# LESR.net
KiCad netlist of a schematic drawn in EAGLE
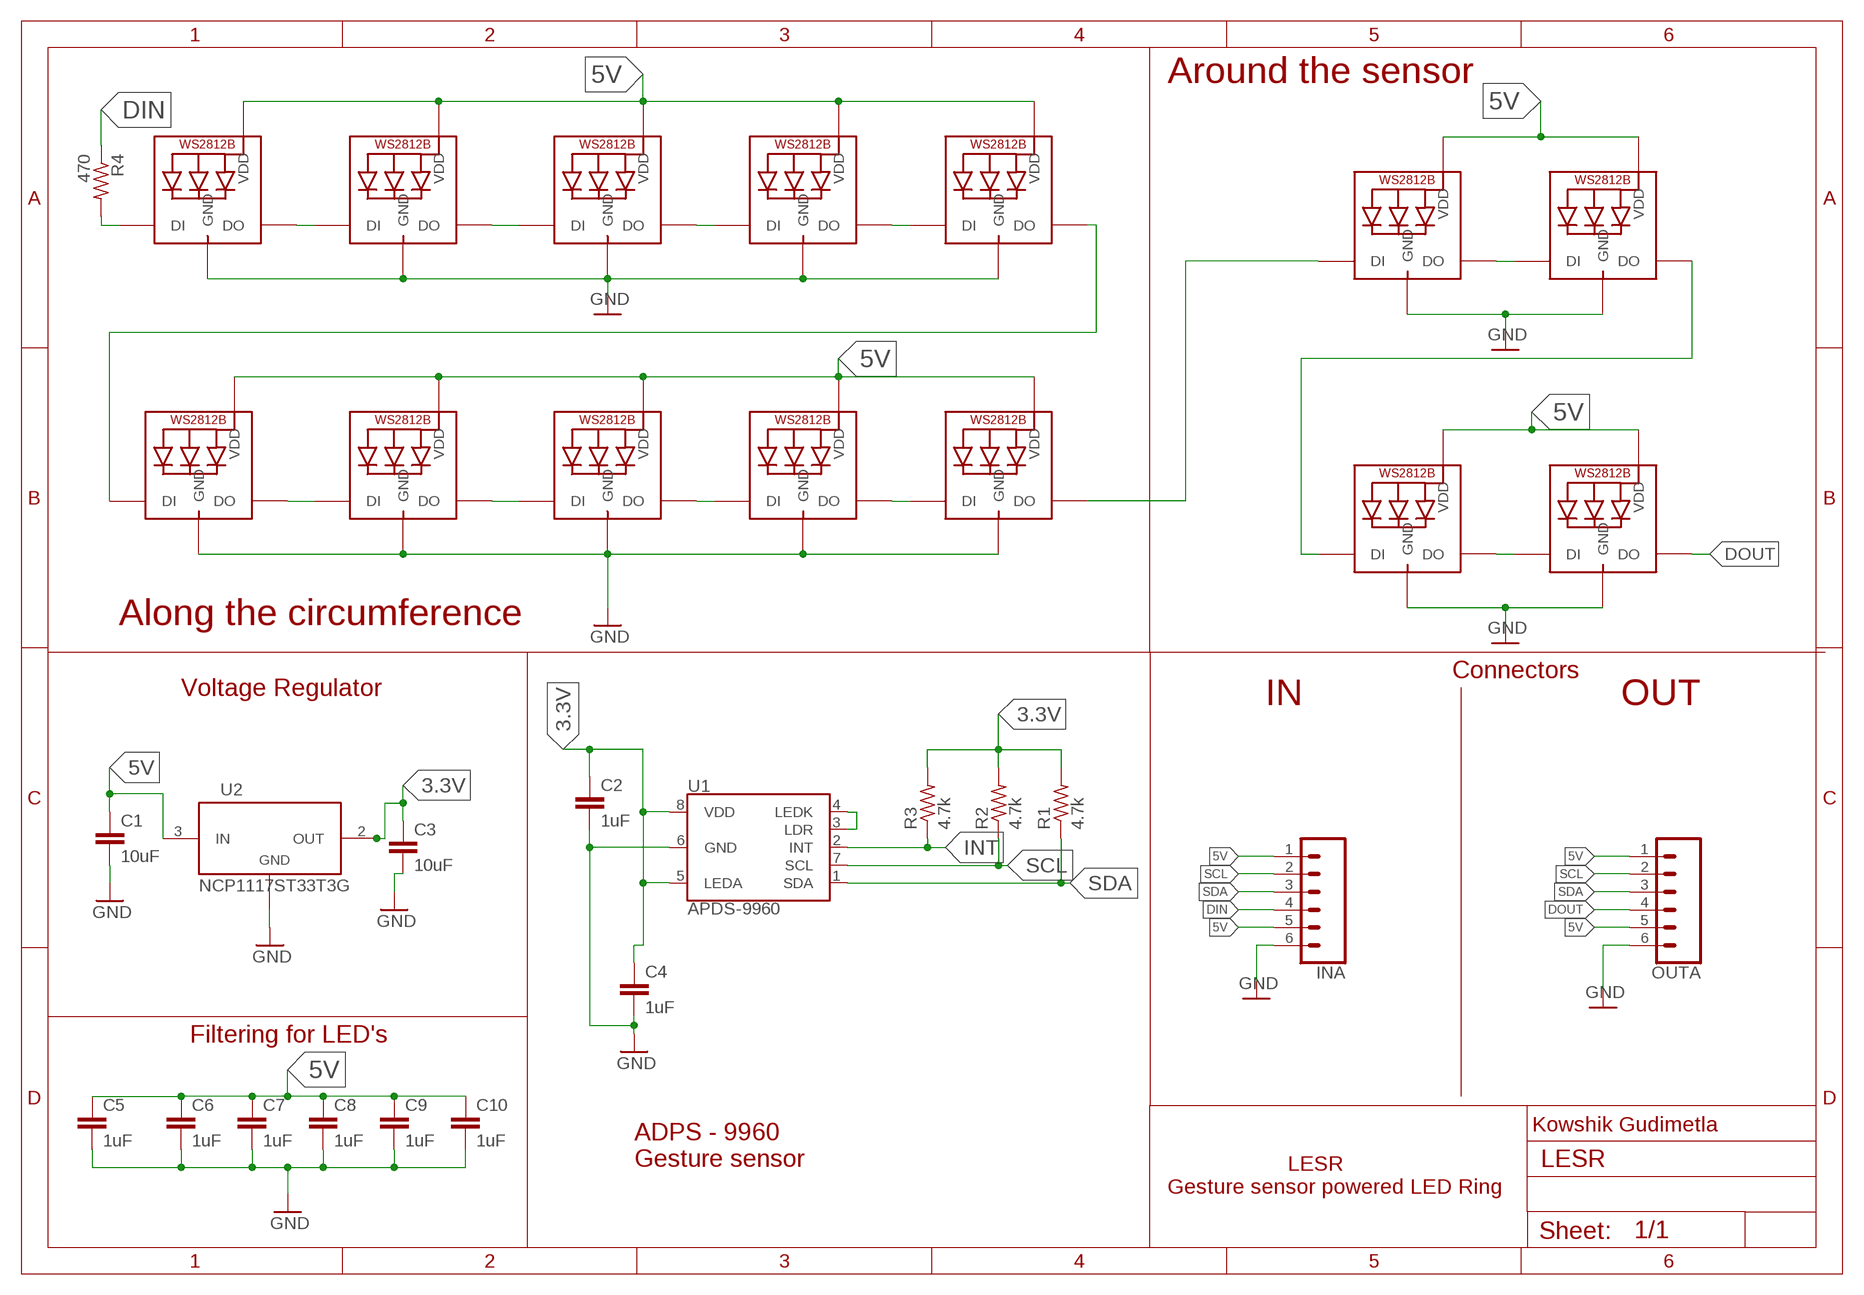
[diagram p0: schematic, sheet 1]

(export (version "E")
  (design (tool "Eeschema 10.0.6"))
  (components
    (comp (ref "C1")
      (value "10uF")
      (footprint "eagle-import:C0603")
      (libsource (lib "eagle-import") (part "C-EUC0603"))
    )
    (comp (ref "C2")
      (value "1uF")
      (footprint "eagle-import:C0603")
      (libsource (lib "eagle-import") (part "C-EUC0603"))
    )
    (comp (ref "C3")
      (value "10uF")
      (footprint "eagle-import:C0603")
      (libsource (lib "eagle-import") (part "C-EUC0603"))
    )
    (comp (ref "C4")
      (value "1uF")
      (footprint "eagle-import:C0603")
      (libsource (lib "eagle-import") (part "C-EUC0603"))
    )
    (comp (ref "C5")
      (value "1uF")
      (footprint "eagle-import:C0603")
      (libsource (lib "eagle-import") (part "C-EUC0603"))
    )
    (comp (ref "C6")
      (value "1uF")
      (footprint "eagle-import:C0603")
      (libsource (lib "eagle-import") (part "C-EUC0603"))
    )
    (comp (ref "C7")
      (value "1uF")
      (footprint "eagle-import:C0603")
      (libsource (lib "eagle-import") (part "C-EUC0603"))
    )
    (comp (ref "C8")
      (value "1uF")
      (footprint "eagle-import:C0603")
      (libsource (lib "eagle-import") (part "C-EUC0603"))
    )
    (comp (ref "C9")
      (value "1uF")
      (footprint "eagle-import:C0603")
      (libsource (lib "eagle-import") (part "C-EUC0603"))
    )
    (comp (ref "C10")
      (value "1uF")
      (footprint "eagle-import:C0603")
      (libsource (lib "eagle-import") (part "C-EUC0603"))
    )
    (comp (ref "IN")
      (value "BM06B-SRSS-TB")
      (footprint "eagle-import:JST-6-SMD-HORI-1.0MM")
      (libsource (lib "eagle-import") (part "JST_6_PIN_HORIZONTAL"))
    )
    (comp (ref "LED1")
      (value "WS2812B5050")
      (footprint "eagle-import:WS2812B")
      (fields (field (name "MF") "SparkFun Electronics") (field (name "MP") "WS2812B"))
      (libsource (lib "eagle-import") (part "WS2812B5050"))
    )
    (comp (ref "LED2")
      (value "WS2812B5050")
      (footprint "eagle-import:WS2812B")
      (fields (field (name "MF") "SparkFun Electronics") (field (name "MP") "WS2812B"))
      (libsource (lib "eagle-import") (part "WS2812B5050"))
    )
    (comp (ref "LED3")
      (value "WS2812B5050")
      (footprint "eagle-import:WS2812B")
      (fields (field (name "MF") "SparkFun Electronics") (field (name "MP") "WS2812B"))
      (libsource (lib "eagle-import") (part "WS2812B5050"))
    )
    (comp (ref "LED4")
      (value "WS2812B5050")
      (footprint "eagle-import:WS2812B")
      (fields (field (name "MF") "SparkFun Electronics") (field (name "MP") "WS2812B"))
      (libsource (lib "eagle-import") (part "WS2812B5050"))
    )
    (comp (ref "LED5")
      (value "WS2812B5050")
      (footprint "eagle-import:WS2812B")
      (fields (field (name "MF") "SparkFun Electronics") (field (name "MP") "WS2812B"))
      (libsource (lib "eagle-import") (part "WS2812B5050"))
    )
    (comp (ref "LED6")
      (value "WS2812B5050")
      (footprint "eagle-import:WS2812B")
      (fields (field (name "MF") "SparkFun Electronics") (field (name "MP") "WS2812B"))
      (libsource (lib "eagle-import") (part "WS2812B5050"))
    )
    (comp (ref "LED7")
      (value "WS2812B5050")
      (footprint "eagle-import:WS2812B")
      (fields (field (name "MF") "SparkFun Electronics") (field (name "MP") "WS2812B"))
      (libsource (lib "eagle-import") (part "WS2812B5050"))
    )
    (comp (ref "LED8")
      (value "WS2812B5050")
      (footprint "eagle-import:WS2812B")
      (fields (field (name "MF") "SparkFun Electronics") (field (name "MP") "WS2812B"))
      (libsource (lib "eagle-import") (part "WS2812B5050"))
    )
    (comp (ref "LED9")
      (value "WS2812B5050")
      (footprint "eagle-import:WS2812B")
      (fields (field (name "MF") "SparkFun Electronics") (field (name "MP") "WS2812B"))
      (libsource (lib "eagle-import") (part "WS2812B5050"))
    )
    (comp (ref "LED10")
      (value "WS2812B5050")
      (footprint "eagle-import:WS2812B")
      (fields (field (name "MF") "SparkFun Electronics") (field (name "MP") "WS2812B"))
      (libsource (lib "eagle-import") (part "WS2812B5050"))
    )
    (comp (ref "LED11")
      (value "WS2812B5050")
      (footprint "eagle-import:WS2812B")
      (fields (field (name "MF") "SparkFun Electronics") (field (name "MP") "WS2812B"))
      (libsource (lib "eagle-import") (part "WS2812B5050"))
    )
    (comp (ref "LED12")
      (value "WS2812B5050")
      (footprint "eagle-import:WS2812B")
      (fields (field (name "MF") "SparkFun Electronics") (field (name "MP") "WS2812B"))
      (libsource (lib "eagle-import") (part "WS2812B5050"))
    )
    (comp (ref "LED13")
      (value "WS2812B5050")
      (footprint "eagle-import:WS2812B")
      (fields (field (name "MF") "SparkFun Electronics") (field (name "MP") "WS2812B"))
      (libsource (lib "eagle-import") (part "WS2812B5050"))
    )
    (comp (ref "LED14")
      (value "WS2812B5050")
      (footprint "eagle-import:WS2812B")
      (fields (field (name "MF") "SparkFun Electronics") (field (name "MP") "WS2812B"))
      (libsource (lib "eagle-import") (part "WS2812B5050"))
    )
    (comp (ref "OUT")
      (value "BM06B-SRSS-TB")
      (footprint "eagle-import:JST-6-SMD-HORI-1.0MM")
      (libsource (lib "eagle-import") (part "JST_6_PIN_HORIZONTAL"))
    )
    (comp (ref "R1")
      (value "4.7k")
      (footprint "eagle-import:R0603")
      (libsource (lib "eagle-import") (part "R-US_R0603"))
    )
    (comp (ref "R2")
      (value "4.7k")
      (footprint "eagle-import:R0603")
      (libsource (lib "eagle-import") (part "R-US_R0603"))
    )
    (comp (ref "R3")
      (value "4.7k")
      (footprint "eagle-import:R0603")
      (libsource (lib "eagle-import") (part "R-US_R0603"))
    )
    (comp (ref "R4")
      (value "470")
      (footprint "eagle-import:R0603")
      (libsource (lib "eagle-import") (part "R-US_R0603"))
    )
    (comp (ref "U1")
      (value "APDS-9960")
      (footprint "eagle-import:APDS-9960")
      (fields (field (name "MF") "Broadcom Limited"))
      (libsource (lib "eagle-import") (part "APDS-9960"))
    )
    (comp (ref "U2")
      (value "NCP1117ST33T3G")
      (footprint "eagle-import:SOT-223")
      (fields
        (field (name "DIGIKEY_PART_NUMBER") "NCP1117ST33T3GOSTR-ND")
        (field (name "MANUFACTURER") "ON Semiconductor")
        (field (name "CREATED_BY") "PCBLayout.com")
      )
      (libsource (lib "eagle-import") (part "NCP1117ST33T3G"))
    )
  )
  (nets
    (net (code "1") (name "3.3V") (class "Default")
      (node (ref "C2") (pin "1") (pinfunction "1_1") (pintype "passive"))
      (node (ref "C3") (pin "1") (pinfunction "1_1") (pintype "passive"))
      (node (ref "C4") (pin "1") (pinfunction "1_1") (pintype "passive"))
      (node (ref "R1") (pin "2") (pinfunction "2_2") (pintype "passive"))
      (node (ref "R2") (pin "2") (pinfunction "2_2") (pintype "passive"))
      (node (ref "R3") (pin "2") (pinfunction "2_2") (pintype "passive"))
      (node (ref "U1") (pin "5") (pinfunction "LEDA_5") (pintype "bidirectional"))
      (node (ref "U1") (pin "8") (pinfunction "VDD_8") (pintype "bidirectional"))
      (node (ref "U2") (pin "2") (pinfunction "OUT_2") (pintype "output"))
      (node (ref "U2") (pin "4") (pinfunction "4_4") (pintype "passive"))
    )
    (net (code "2") (name "5V") (class "Default")
      (node (ref "C1") (pin "1") (pinfunction "1_1") (pintype "passive"))
      (node (ref "C10") (pin "1") (pinfunction "1_1") (pintype "passive"))
      (node (ref "C5") (pin "1") (pinfunction "1_1") (pintype "passive"))
      (node (ref "C6") (pin "1") (pinfunction "1_1") (pintype "passive"))
      (node (ref "C7") (pin "1") (pinfunction "1_1") (pintype "passive"))
      (node (ref "C8") (pin "1") (pinfunction "1_1") (pintype "passive"))
      (node (ref "C9") (pin "1") (pinfunction "1_1") (pintype "passive"))
      (node (ref "IN") (pin "1") (pinfunction "1_1") (pintype "passive"))
      (node (ref "IN") (pin "5") (pinfunction "5_5") (pintype "passive"))
      (node (ref "LED1") (pin "1-VDD") (pinfunction "VDD_1-VDD") (pintype "power_in"))
      (node (ref "LED10") (pin "1-VDD") (pinfunction "VDD_1-VDD") (pintype "power_in"))
      (node (ref "LED11") (pin "1-VDD") (pinfunction "VDD_1-VDD") (pintype "power_in"))
      (node (ref "LED12") (pin "1-VDD") (pinfunction "VDD_1-VDD") (pintype "power_in"))
      (node (ref "LED13") (pin "1-VDD") (pinfunction "VDD_1-VDD") (pintype "power_in"))
      (node (ref "LED14") (pin "1-VDD") (pinfunction "VDD_1-VDD") (pintype "power_in"))
      (node (ref "LED2") (pin "1-VDD") (pinfunction "VDD_1-VDD") (pintype "power_in"))
      (node (ref "LED3") (pin "1-VDD") (pinfunction "VDD_1-VDD") (pintype "power_in"))
      (node (ref "LED4") (pin "1-VDD") (pinfunction "VDD_1-VDD") (pintype "power_in"))
      (node (ref "LED5") (pin "1-VDD") (pinfunction "VDD_1-VDD") (pintype "power_in"))
      (node (ref "LED6") (pin "1-VDD") (pinfunction "VDD_1-VDD") (pintype "power_in"))
      (node (ref "LED7") (pin "1-VDD") (pinfunction "VDD_1-VDD") (pintype "power_in"))
      (node (ref "LED8") (pin "1-VDD") (pinfunction "VDD_1-VDD") (pintype "power_in"))
      (node (ref "LED9") (pin "1-VDD") (pinfunction "VDD_1-VDD") (pintype "power_in"))
      (node (ref "OUT") (pin "1") (pinfunction "1_1") (pintype "passive"))
      (node (ref "OUT") (pin "5") (pinfunction "5_5") (pintype "passive"))
      (node (ref "U2") (pin "3") (pinfunction "IN_3") (pintype "input"))
    )
    (net (code "3") (name "DIN") (class "Default")
      (node (ref "IN") (pin "4") (pinfunction "4_4") (pintype "passive"))
      (node (ref "R4") (pin "1") (pinfunction "1_1") (pintype "passive"))
    )
    (net (code "4") (name "DOUT") (class "Default")
      (node (ref "LED14") (pin "2-DOUT") (pinfunction "DO_2-DOUT") (pintype "output"))
      (node (ref "OUT") (pin "4") (pinfunction "4_4") (pintype "passive"))
    )
    (net (code "5") (name "GND") (class "Default")
      (node (ref "C1") (pin "2") (pinfunction "2_2") (pintype "passive"))
      (node (ref "C10") (pin "2") (pinfunction "2_2") (pintype "passive"))
      (node (ref "C2") (pin "2") (pinfunction "2_2") (pintype "passive"))
      (node (ref "C3") (pin "2") (pinfunction "2_2") (pintype "passive"))
      (node (ref "C4") (pin "2") (pinfunction "2_2") (pintype "passive"))
      (node (ref "C5") (pin "2") (pinfunction "2_2") (pintype "passive"))
      (node (ref "C6") (pin "2") (pinfunction "2_2") (pintype "passive"))
      (node (ref "C7") (pin "2") (pinfunction "2_2") (pintype "passive"))
      (node (ref "C8") (pin "2") (pinfunction "2_2") (pintype "passive"))
      (node (ref "C9") (pin "2") (pinfunction "2_2") (pintype "passive"))
      (node (ref "IN") (pin "6") (pinfunction "6_6") (pintype "passive"))
      (node (ref "LED1") (pin "3-GND") (pinfunction "GND_3-GND") (pintype "power_in"))
      (node (ref "LED10") (pin "3-GND") (pinfunction "GND_3-GND") (pintype "power_in"))
      (node (ref "LED11") (pin "3-GND") (pinfunction "GND_3-GND") (pintype "power_in"))
      (node (ref "LED12") (pin "3-GND") (pinfunction "GND_3-GND") (pintype "power_in"))
      (node (ref "LED13") (pin "3-GND") (pinfunction "GND_3-GND") (pintype "power_in"))
      (node (ref "LED14") (pin "3-GND") (pinfunction "GND_3-GND") (pintype "power_in"))
      (node (ref "LED2") (pin "3-GND") (pinfunction "GND_3-GND") (pintype "power_in"))
      (node (ref "LED3") (pin "3-GND") (pinfunction "GND_3-GND") (pintype "power_in"))
      (node (ref "LED4") (pin "3-GND") (pinfunction "GND_3-GND") (pintype "power_in"))
      (node (ref "LED5") (pin "3-GND") (pinfunction "GND_3-GND") (pintype "power_in"))
      (node (ref "LED6") (pin "3-GND") (pinfunction "GND_3-GND") (pintype "power_in"))
      (node (ref "LED7") (pin "3-GND") (pinfunction "GND_3-GND") (pintype "power_in"))
      (node (ref "LED8") (pin "3-GND") (pinfunction "GND_3-GND") (pintype "power_in"))
      (node (ref "LED9") (pin "3-GND") (pinfunction "GND_3-GND") (pintype "power_in"))
      (node (ref "OUT") (pin "6") (pinfunction "6_6") (pintype "passive"))
      (node (ref "U1") (pin "6") (pinfunction "GND_6") (pintype "bidirectional"))
      (node (ref "U2") (pin "1") (pinfunction "ADJ/GND_1") (pintype "power_in"))
    )
    (net (code "6") (name "INT") (class "Default")
      (node (ref "R3") (pin "1") (pinfunction "1_1") (pintype "passive"))
      (node (ref "U1") (pin "2") (pinfunction "INT_2") (pintype "bidirectional"))
    )
    (net (code "7") (name "Net-(LED1-DI)") (class "Default")
      (node (ref "LED1") (pin "4-DIN") (pinfunction "DI_4-DIN") (pintype "input"))
      (node (ref "R4") (pin "2") (pinfunction "2_2") (pintype "passive"))
    )
    (net (code "8") (name "Net-(LED1-DO)") (class "Default")
      (node (ref "LED1") (pin "2-DOUT") (pinfunction "DO_2-DOUT") (pintype "output"))
      (node (ref "LED2") (pin "4-DIN") (pinfunction "DI_4-DIN") (pintype "input"))
    )
    (net (code "9") (name "Net-(LED2-DO)") (class "Default")
      (node (ref "LED2") (pin "2-DOUT") (pinfunction "DO_2-DOUT") (pintype "output"))
      (node (ref "LED3") (pin "4-DIN") (pinfunction "DI_4-DIN") (pintype "input"))
    )
    (net (code "10") (name "Net-(LED3-DO)") (class "Default")
      (node (ref "LED3") (pin "2-DOUT") (pinfunction "DO_2-DOUT") (pintype "output"))
      (node (ref "LED4") (pin "4-DIN") (pinfunction "DI_4-DIN") (pintype "input"))
    )
    (net (code "11") (name "Net-(LED4-DO)") (class "Default")
      (node (ref "LED4") (pin "2-DOUT") (pinfunction "DO_2-DOUT") (pintype "output"))
      (node (ref "LED5") (pin "4-DIN") (pinfunction "DI_4-DIN") (pintype "input"))
    )
    (net (code "12") (name "Net-(LED5-DO)") (class "Default")
      (node (ref "LED5") (pin "2-DOUT") (pinfunction "DO_2-DOUT") (pintype "output"))
      (node (ref "LED6") (pin "4-DIN") (pinfunction "DI_4-DIN") (pintype "input"))
    )
    (net (code "13") (name "Net-(LED6-DO)") (class "Default")
      (node (ref "LED6") (pin "2-DOUT") (pinfunction "DO_2-DOUT") (pintype "output"))
      (node (ref "LED7") (pin "4-DIN") (pinfunction "DI_4-DIN") (pintype "input"))
    )
    (net (code "14") (name "Net-(LED7-DO)") (class "Default")
      (node (ref "LED7") (pin "2-DOUT") (pinfunction "DO_2-DOUT") (pintype "output"))
      (node (ref "LED8") (pin "4-DIN") (pinfunction "DI_4-DIN") (pintype "input"))
    )
    (net (code "15") (name "Net-(LED8-DO)") (class "Default")
      (node (ref "LED8") (pin "2-DOUT") (pinfunction "DO_2-DOUT") (pintype "output"))
      (node (ref "LED9") (pin "4-DIN") (pinfunction "DI_4-DIN") (pintype "input"))
    )
    (net (code "16") (name "Net-(LED10-DI)") (class "Default")
      (node (ref "LED10") (pin "4-DIN") (pinfunction "DI_4-DIN") (pintype "input"))
      (node (ref "LED9") (pin "2-DOUT") (pinfunction "DO_2-DOUT") (pintype "output"))
    )
    (net (code "17") (name "Net-(LED10-DO)") (class "Default")
      (node (ref "LED10") (pin "2-DOUT") (pinfunction "DO_2-DOUT") (pintype "output"))
      (node (ref "LED11") (pin "4-DIN") (pinfunction "DI_4-DIN") (pintype "input"))
    )
    (net (code "18") (name "Net-(LED11-DO)") (class "Default")
      (node (ref "LED11") (pin "2-DOUT") (pinfunction "DO_2-DOUT") (pintype "output"))
      (node (ref "LED12") (pin "4-DIN") (pinfunction "DI_4-DIN") (pintype "input"))
    )
    (net (code "19") (name "Net-(LED12-DO)") (class "Default")
      (node (ref "LED12") (pin "2-DOUT") (pinfunction "DO_2-DOUT") (pintype "output"))
      (node (ref "LED13") (pin "4-DIN") (pinfunction "DI_4-DIN") (pintype "input"))
    )
    (net (code "20") (name "Net-(LED13-DO)") (class "Default")
      (node (ref "LED13") (pin "2-DOUT") (pinfunction "DO_2-DOUT") (pintype "output"))
      (node (ref "LED14") (pin "4-DIN") (pinfunction "DI_4-DIN") (pintype "input"))
    )
    (net (code "21") (name "Net-(U1-LDR)") (class "Default")
      (node (ref "U1") (pin "3") (pinfunction "LDR_3") (pintype "bidirectional"))
      (node (ref "U1") (pin "4") (pinfunction "LEDK_4") (pintype "bidirectional"))
    )
    (net (code "22") (name "SCL") (class "Default")
      (node (ref "IN") (pin "2") (pinfunction "2_2") (pintype "passive"))
      (node (ref "OUT") (pin "2") (pinfunction "2_2") (pintype "passive"))
      (node (ref "R2") (pin "1") (pinfunction "1_1") (pintype "passive"))
      (node (ref "U1") (pin "7") (pinfunction "SCL_7") (pintype "bidirectional"))
    )
    (net (code "23") (name "SDA") (class "Default")
      (node (ref "IN") (pin "3") (pinfunction "3_3") (pintype "passive"))
      (node (ref "OUT") (pin "3") (pinfunction "3_3") (pintype "passive"))
      (node (ref "R1") (pin "1") (pinfunction "1_1") (pintype "passive"))
      (node (ref "U1") (pin "1") (pinfunction "SDA_1") (pintype "bidirectional"))
    )
  )
)
